# FoamBot_Arduino_Pololu_servo_r1.net
KiCad netlist of a schematic drawn in EAGLE
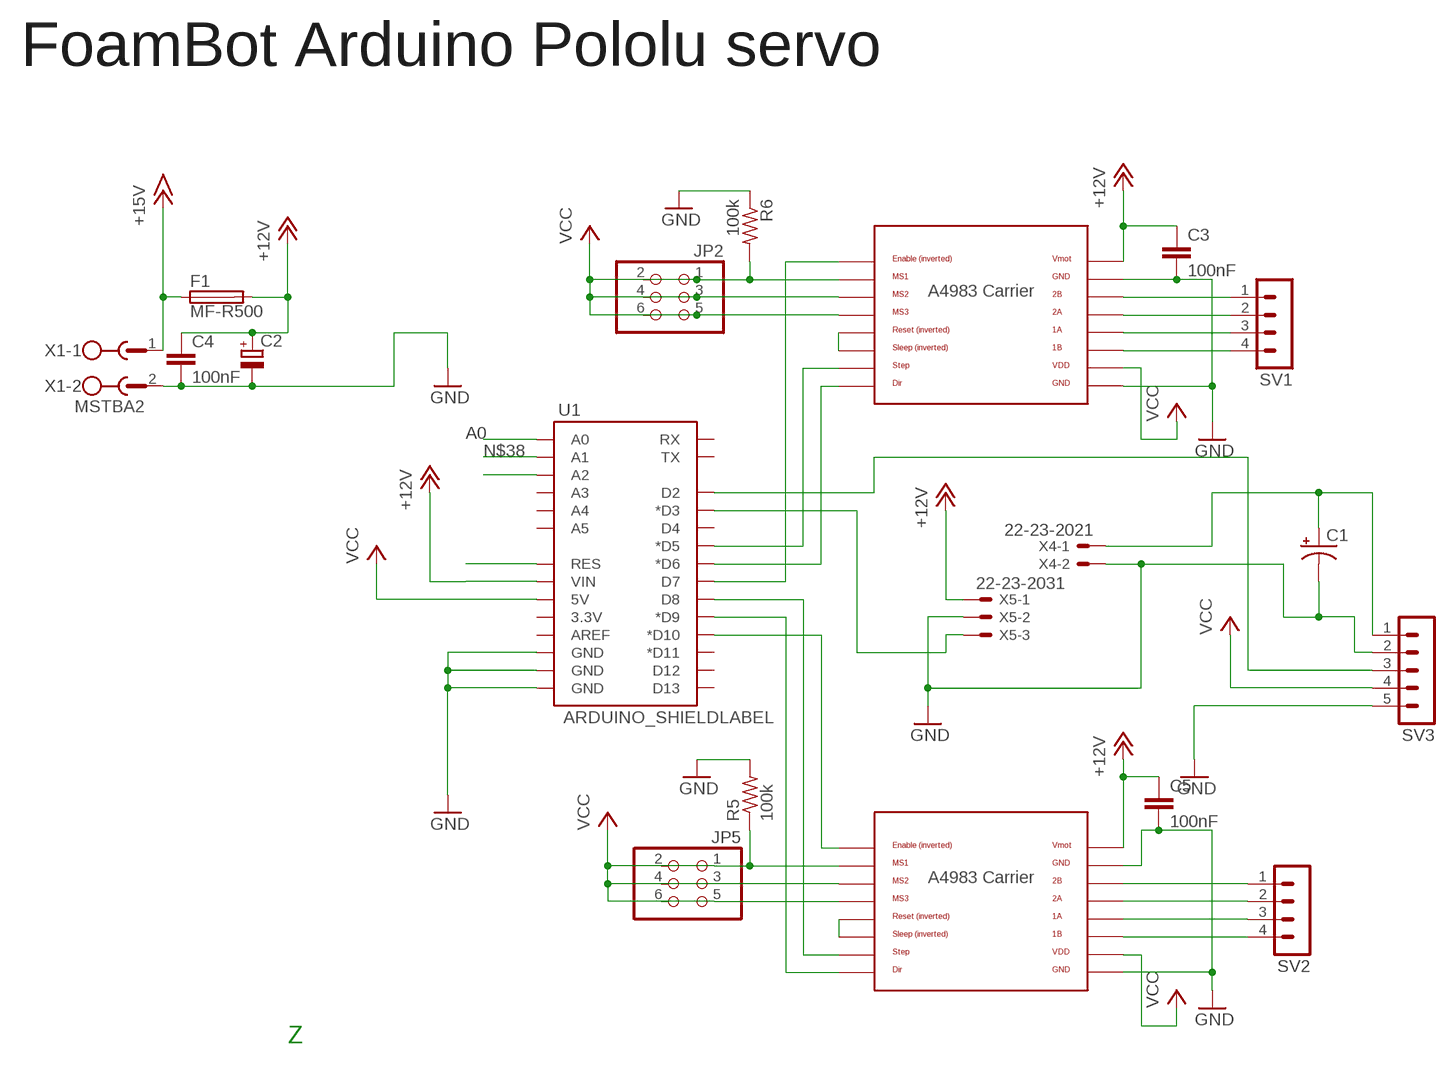
[diagram p0: schematic, sheet 1]

(export (version "E")
  (design (tool "Eeschema 10.0.6"))
  (components
    (comp (ref "C1")
      (value "CPOL-USE5-10.5")
      (footprint "eagle-import:E5-10,5")
      (libsource (lib "eagle-import") (part "CPOL-USE5-10.5"))
    )
    (comp (ref "C2")
      (value "CPOL-EUE7.5-16")
      (footprint "eagle-import:E7,5-16")
      (libsource (lib "eagle-import") (part "CPOL-EUE7.5-16"))
    )
    (comp (ref "C3")
      (value "100nF")
      (footprint "eagle-import:C2.5-3")
      (libsource (lib "eagle-import") (part "C2,5-3"))
    )
    (comp (ref "C4")
      (value "100nF")
      (footprint "eagle-import:C2.5-3")
      (libsource (lib "eagle-import") (part "C2,5-3"))
    )
    (comp (ref "C5")
      (value "100nF")
      (footprint "eagle-import:C2.5-3")
      (libsource (lib "eagle-import") (part "C2,5-3"))
    )
    (comp (ref "F1")
      (value "MF-R500")
      (footprint "eagle-import:LITTLEFUSE")
      (libsource (lib "eagle-import") (part "LITTLEFUSE"))
    )
    (comp (ref "JP2")
      (value "PINHD-2X3")
      (footprint "eagle-import:2X03")
      (libsource (lib "eagle-import") (part "PINHD-2X3"))
    )
    (comp (ref "JP5")
      (value "PINHD-2X3")
      (footprint "eagle-import:2X03")
      (libsource (lib "eagle-import") (part "PINHD-2X3"))
    )
    (comp (ref "R5")
      (value "100k")
      (footprint "eagle-import:0207_7")
      (libsource (lib "eagle-import") (part "R-US_0207/7"))
    )
    (comp (ref "R6")
      (value "100k")
      (footprint "eagle-import:0207_7")
      (libsource (lib "eagle-import") (part "R-US_0207/7"))
    )
    (comp (ref "SV1")
      (value "MA04-1")
      (footprint "eagle-import:MA04-1")
      (libsource (lib "eagle-import") (part "MA04-1"))
    )
    (comp (ref "SV2")
      (value "MA04-1")
      (footprint "eagle-import:MA04-1")
      (libsource (lib "eagle-import") (part "MA04-1"))
    )
    (comp (ref "SV3")
      (value "MA05-1")
      (footprint "eagle-import:MA05-1")
      (libsource (lib "eagle-import") (part "MA05-1"))
    )
    (comp (ref "U1")
      (value "ARDUINO_SHIELDLABEL")
      (footprint "eagle-import:DUEMILANOVE_SHIELD")
      (libsource (lib "eagle-import") (part "ARDUINO_SHIELDLABEL"))
    )
    (comp (ref "U2")
      (value "POLOLU_A4983CARRIER")
      (footprint "eagle-import:A4983CARRIER")
      (libsource (lib "eagle-import") (part "POLOLU_A4983CARRIER"))
    )
    (comp (ref "U3")
      (value "POLOLU_A4983CARRIER")
      (footprint "eagle-import:A4983CARRIER")
      (libsource (lib "eagle-import") (part "POLOLU_A4983CARRIER"))
    )
    (comp (ref "X1")
      (value "MSTBA2")
      (footprint "eagle-import:MSTBA2")
      (fields (field (name "MF") "FARNELL") (field (name "MPN") "1757242"))
      (libsource (lib "eagle-import") (part "MSTBA2"))
    )
    (comp (ref "X4")
      (value "22-23-2021")
      (footprint "eagle-import:22-23-2021")
      (fields (field (name "MF") "MOLEX"))
      (libsource (lib "eagle-import") (part "22-23-2021"))
    )
    (comp (ref "X5")
      (value "22-23-2031")
      (footprint "eagle-import:22-23-2031")
      (fields (field (name "MF") "MOLEX"))
      (libsource (lib "eagle-import") (part "22-23-2031"))
    )
  )
  (nets
    (net (code "1") (name "+12V") (class "Default")
      (node (ref "C2") (pin "+") (pinfunction "+_+") (pintype "passive"))
      (node (ref "C3") (pin "1") (pinfunction "1_1") (pintype "passive"))
      (node (ref "C4") (pin "1") (pinfunction "1_1") (pintype "passive"))
      (node (ref "C5") (pin "1") (pinfunction "1_1") (pintype "passive"))
      (node (ref "F1") (pin "2") (pinfunction "2_2") (pintype "passive"))
      (node (ref "U1") (pin "VIN") (pinfunction "VIN_VIN") (pintype "bidirectional"))
      (node (ref "U2") (pin "VMOT") (pinfunction "VMOT_VMOT") (pintype "power_in"))
      (node (ref "U3") (pin "VMOT") (pinfunction "VMOT_VMOT") (pintype "power_in"))
      (node (ref "X5") (pin "1") (pinfunction "S_1") (pintype "passive"))
    )
    (net (code "2") (name "+15V") (class "Default")
      (node (ref "F1") (pin "1") (pinfunction "1_1") (pintype "passive"))
      (node (ref "X1") (pin "1") (pinfunction "1_1") (pintype "passive"))
    )
    (net (code "3") (name "/A0") (class "Default")
      (node (ref "U1") (pin "A0") (pinfunction "A0_A0") (pintype "bidirectional"))
    )
    (net (code "4") (name "/N$38") (class "Default")
      (node (ref "U1") (pin "A1") (pinfunction "A1_A1") (pintype "bidirectional"))
    )
    (net (code "5") (name "GND") (class "Default")
      (node (ref "C1") (pin "-") (pinfunction "-_-") (pintype "passive"))
      (node (ref "C2") (pin "-") (pinfunction "-_-") (pintype "passive"))
      (node (ref "C3") (pin "2") (pinfunction "2_2") (pintype "passive"))
      (node (ref "C4") (pin "2") (pinfunction "2_2") (pintype "passive"))
      (node (ref "C5") (pin "2") (pinfunction "2_2") (pintype "passive"))
      (node (ref "R5") (pin "2") (pinfunction "2_2") (pintype "passive"))
      (node (ref "R6") (pin "1") (pinfunction "1_1") (pintype "passive"))
      (node (ref "SV3") (pin "2") (pinfunction "2_2") (pintype "passive"))
      (node (ref "SV3") (pin "5") (pinfunction "5_5") (pintype "passive"))
      (node (ref "U1") (pin "GND@0") (pinfunction "GND_GND@0") (pintype "bidirectional"))
      (node (ref "U1") (pin "GND@1") (pinfunction "GND_GND@1") (pintype "bidirectional"))
      (node (ref "U1") (pin "GND@2") (pinfunction "GND_GND@2") (pintype "bidirectional"))
      (node (ref "U2") (pin "GND") (pinfunction "GND_GND") (pintype "power_in"))
      (node (ref "U2") (pin "GND@0") (pinfunction "GND_GND@0") (pintype "power_in"))
      (node (ref "U3") (pin "GND") (pinfunction "GND_GND") (pintype "power_in"))
      (node (ref "U3") (pin "GND@0") (pinfunction "GND_GND@0") (pintype "power_in"))
      (node (ref "X1") (pin "2") (pinfunction "1_2") (pintype "passive"))
      (node (ref "X4") (pin "2") (pinfunction "S_2") (pintype "passive"))
      (node (ref "X5") (pin "2") (pinfunction "S_2") (pintype "passive"))
    )
    (net (code "6") (name "Net-(SV1-Pad1)") (class "Default")
      (node (ref "SV1") (pin "1") (pinfunction "1_1") (pintype "passive"))
      (node (ref "U2") (pin "2B") (pinfunction "2B_2B") (pintype "output"))
    )
    (net (code "7") (name "Net-(SV1-Pad2)") (class "Default")
      (node (ref "SV1") (pin "2") (pinfunction "2_2") (pintype "passive"))
      (node (ref "U2") (pin "2A") (pinfunction "2A_2A") (pintype "output"))
    )
    (net (code "8") (name "Net-(SV1-Pad3)") (class "Default")
      (node (ref "SV1") (pin "3") (pinfunction "3_3") (pintype "passive"))
      (node (ref "U2") (pin "1A") (pinfunction "1A_1A") (pintype "output"))
    )
    (net (code "9") (name "Net-(SV1-Pad4)") (class "Default")
      (node (ref "SV1") (pin "4") (pinfunction "4_4") (pintype "passive"))
      (node (ref "U2") (pin "1B") (pinfunction "1B_1B") (pintype "output"))
    )
    (net (code "10") (name "Net-(SV2-Pad1)") (class "Default")
      (node (ref "SV2") (pin "1") (pinfunction "1_1") (pintype "passive"))
      (node (ref "U3") (pin "2B") (pinfunction "2B_2B") (pintype "output"))
    )
    (net (code "11") (name "Net-(SV2-Pad2)") (class "Default")
      (node (ref "SV2") (pin "2") (pinfunction "2_2") (pintype "passive"))
      (node (ref "U3") (pin "2A") (pinfunction "2A_2A") (pintype "output"))
    )
    (net (code "12") (name "Net-(SV2-Pad3)") (class "Default")
      (node (ref "SV2") (pin "3") (pinfunction "3_3") (pintype "passive"))
      (node (ref "U3") (pin "1A") (pinfunction "1A_1A") (pintype "output"))
    )
    (net (code "13") (name "Net-(SV2-Pad4)") (class "Default")
      (node (ref "SV2") (pin "4") (pinfunction "4_4") (pintype "passive"))
      (node (ref "U3") (pin "1B") (pinfunction "1B_1B") (pintype "output"))
    )
    (net (code "14") (name "Net-(SV3-Pad3)") (class "Default")
      (node (ref "SV3") (pin "3") (pinfunction "3_3") (pintype "passive"))
      (node (ref "U1") (pin "D2") (pinfunction "D2_D2") (pintype "bidirectional"))
    )
    (net (code "15") (name "Net-(U1-*D3)") (class "Default")
      (node (ref "U1") (pin "D3") (pinfunction "*D3_D3") (pintype "bidirectional"))
      (node (ref "X5") (pin "3") (pinfunction "S_3") (pintype "passive"))
    )
    (net (code "16") (name "Net-(U1-*D5)") (class "Default")
      (node (ref "U1") (pin "D5") (pinfunction "*D5_D5") (pintype "bidirectional"))
      (node (ref "U2") (pin "STEP") (pinfunction "STEP_STEP") (pintype "input"))
    )
    (net (code "17") (name "Net-(U1-*D6)") (class "Default")
      (node (ref "U1") (pin "D6") (pinfunction "*D6_D6") (pintype "bidirectional"))
      (node (ref "U2") (pin "DIR") (pinfunction "DIR_DIR") (pintype "input"))
    )
    (net (code "18") (name "Net-(U1-*D9)") (class "Default")
      (node (ref "U1") (pin "D9") (pinfunction "*D9_D9") (pintype "bidirectional"))
      (node (ref "U3") (pin "DIR") (pinfunction "DIR_DIR") (pintype "input"))
    )
    (net (code "19") (name "Net-(U1-*D10)") (class "Default")
      (node (ref "U1") (pin "D10") (pinfunction "*D10_D10") (pintype "bidirectional"))
      (node (ref "U3") (pin "EN") (pinfunction "EN_EN") (pintype "input"))
    )
    (net (code "20") (name "Net-(U1-PadD7)") (class "Default")
      (node (ref "U1") (pin "D7") (pinfunction "D7_D7") (pintype "bidirectional"))
      (node (ref "U2") (pin "EN") (pinfunction "EN_EN") (pintype "input"))
    )
    (net (code "21") (name "Net-(U1-PadD8)") (class "Default")
      (node (ref "U1") (pin "D8") (pinfunction "D8_D8") (pintype "bidirectional"))
      (node (ref "U3") (pin "STEP") (pinfunction "STEP_STEP") (pintype "input"))
    )
    (net (code "22") (name "Net-(U2-SLEEP)") (class "Default")
      (node (ref "U2") (pin "RST") (pinfunction "RST_RST") (pintype "input"))
      (node (ref "U2") (pin "SLP") (pinfunction "SLEEP_SLP") (pintype "input"))
    )
    (net (code "23") (name "Net-(U3-SLEEP)") (class "Default")
      (node (ref "U3") (pin "RST") (pinfunction "RST_RST") (pintype "input"))
      (node (ref "U3") (pin "SLP") (pinfunction "SLEEP_SLP") (pintype "input"))
    )
    (net (code "24") (name "Net-(X4A-S)") (class "Default")
      (node (ref "C1") (pin "+") (pinfunction "+_+") (pintype "passive"))
      (node (ref "SV3") (pin "1") (pinfunction "1_1") (pintype "passive"))
      (node (ref "X4") (pin "1") (pinfunction "S_1") (pintype "passive"))
    )
    (net (code "25") (name "VCC") (class "Default")
      (node (ref "JP2") (pin "1") (pinfunction "1_1") (pintype "passive"))
      (node (ref "JP2") (pin "2") (pinfunction "2_2") (pintype "passive"))
      (node (ref "JP2") (pin "3") (pinfunction "3_3") (pintype "passive"))
      (node (ref "JP2") (pin "4") (pinfunction "4_4") (pintype "passive"))
      (node (ref "JP2") (pin "5") (pinfunction "5_5") (pintype "passive"))
      (node (ref "JP2") (pin "6") (pinfunction "6_6") (pintype "passive"))
      (node (ref "JP5") (pin "1") (pinfunction "1_1") (pintype "passive"))
      (node (ref "JP5") (pin "2") (pinfunction "2_2") (pintype "passive"))
      (node (ref "JP5") (pin "3") (pinfunction "3_3") (pintype "passive"))
      (node (ref "JP5") (pin "4") (pinfunction "4_4") (pintype "passive"))
      (node (ref "JP5") (pin "5") (pinfunction "5_5") (pintype "passive"))
      (node (ref "JP5") (pin "6") (pinfunction "6_6") (pintype "passive"))
      (node (ref "R5") (pin "1") (pinfunction "1_1") (pintype "passive"))
      (node (ref "R6") (pin "2") (pinfunction "2_2") (pintype "passive"))
      (node (ref "SV3") (pin "4") (pinfunction "4_4") (pintype "passive"))
      (node (ref "U1") (pin "5V") (pinfunction "5V_5V") (pintype "bidirectional"))
      (node (ref "U2") (pin "MS1") (pinfunction "MS1_MS1") (pintype "input"))
      (node (ref "U2") (pin "MS2") (pinfunction "MS2_MS2") (pintype "input"))
      (node (ref "U2") (pin "MS3") (pinfunction "MS3_MS3") (pintype "input"))
      (node (ref "U2") (pin "VDD") (pinfunction "VDD_VDD") (pintype "power_in"))
      (node (ref "U3") (pin "MS1") (pinfunction "MS1_MS1") (pintype "input"))
      (node (ref "U3") (pin "MS2") (pinfunction "MS2_MS2") (pintype "input"))
      (node (ref "U3") (pin "MS3") (pinfunction "MS3_MS3") (pintype "input"))
      (node (ref "U3") (pin "VDD") (pinfunction "VDD_VDD") (pintype "power_in"))
    )
    (net (code "26") (name "unconnected-(U1-*D11-PadD11)") (class "Default")
      (node (ref "U1") (pin "D11") (pinfunction "*D11_D11") (pintype "bidirectional"))
    )
    (net (code "27") (name "unconnected-(U1-Pad3.3V)") (class "Default")
      (node (ref "U1") (pin "3.3V") (pinfunction "3.3V_3.3V") (pintype "bidirectional"))
    )
    (net (code "28") (name "unconnected-(U1-PadA2)") (class "Default")
      (node (ref "U1") (pin "A2") (pinfunction "A2_A2") (pintype "bidirectional"))
    )
    (net (code "29") (name "unconnected-(U1-PadA3)") (class "Default")
      (node (ref "U1") (pin "A3") (pinfunction "A3_A3") (pintype "bidirectional"))
    )
    (net (code "30") (name "unconnected-(U1-PadA4)") (class "Default")
      (node (ref "U1") (pin "A4") (pinfunction "A4_A4") (pintype "bidirectional"))
    )
    (net (code "31") (name "unconnected-(U1-PadA5)") (class "Default")
      (node (ref "U1") (pin "A5") (pinfunction "A5_A5") (pintype "bidirectional"))
    )
    (net (code "32") (name "unconnected-(U1-PadAREF)") (class "Default")
      (node (ref "U1") (pin "AREF") (pinfunction "AREF_AREF") (pintype "bidirectional"))
    )
    (net (code "33") (name "unconnected-(U1-PadD4)") (class "Default")
      (node (ref "U1") (pin "D4") (pinfunction "D4_D4") (pintype "bidirectional"))
    )
    (net (code "34") (name "unconnected-(U1-PadD12)") (class "Default")
      (node (ref "U1") (pin "D12") (pinfunction "D12_D12") (pintype "bidirectional"))
    )
    (net (code "35") (name "unconnected-(U1-PadD13)") (class "Default")
      (node (ref "U1") (pin "D13") (pinfunction "D13_D13") (pintype "bidirectional"))
    )
    (net (code "36") (name "unconnected-(U1-PadRES)") (class "Default")
      (node (ref "U1") (pin "RES") (pinfunction "RES_RES") (pintype "bidirectional"))
    )
    (net (code "37") (name "unconnected-(U1-PadRX)") (class "Default")
      (node (ref "U1") (pin "RX") (pinfunction "RX_RX") (pintype "bidirectional"))
    )
    (net (code "38") (name "unconnected-(U1-PadTX)") (class "Default")
      (node (ref "U1") (pin "TX") (pinfunction "TX_TX") (pintype "bidirectional"))
    )
  )
)
